# Sensor_Connection.net
KiCad netlist of a schematic drawn in Altium Designer
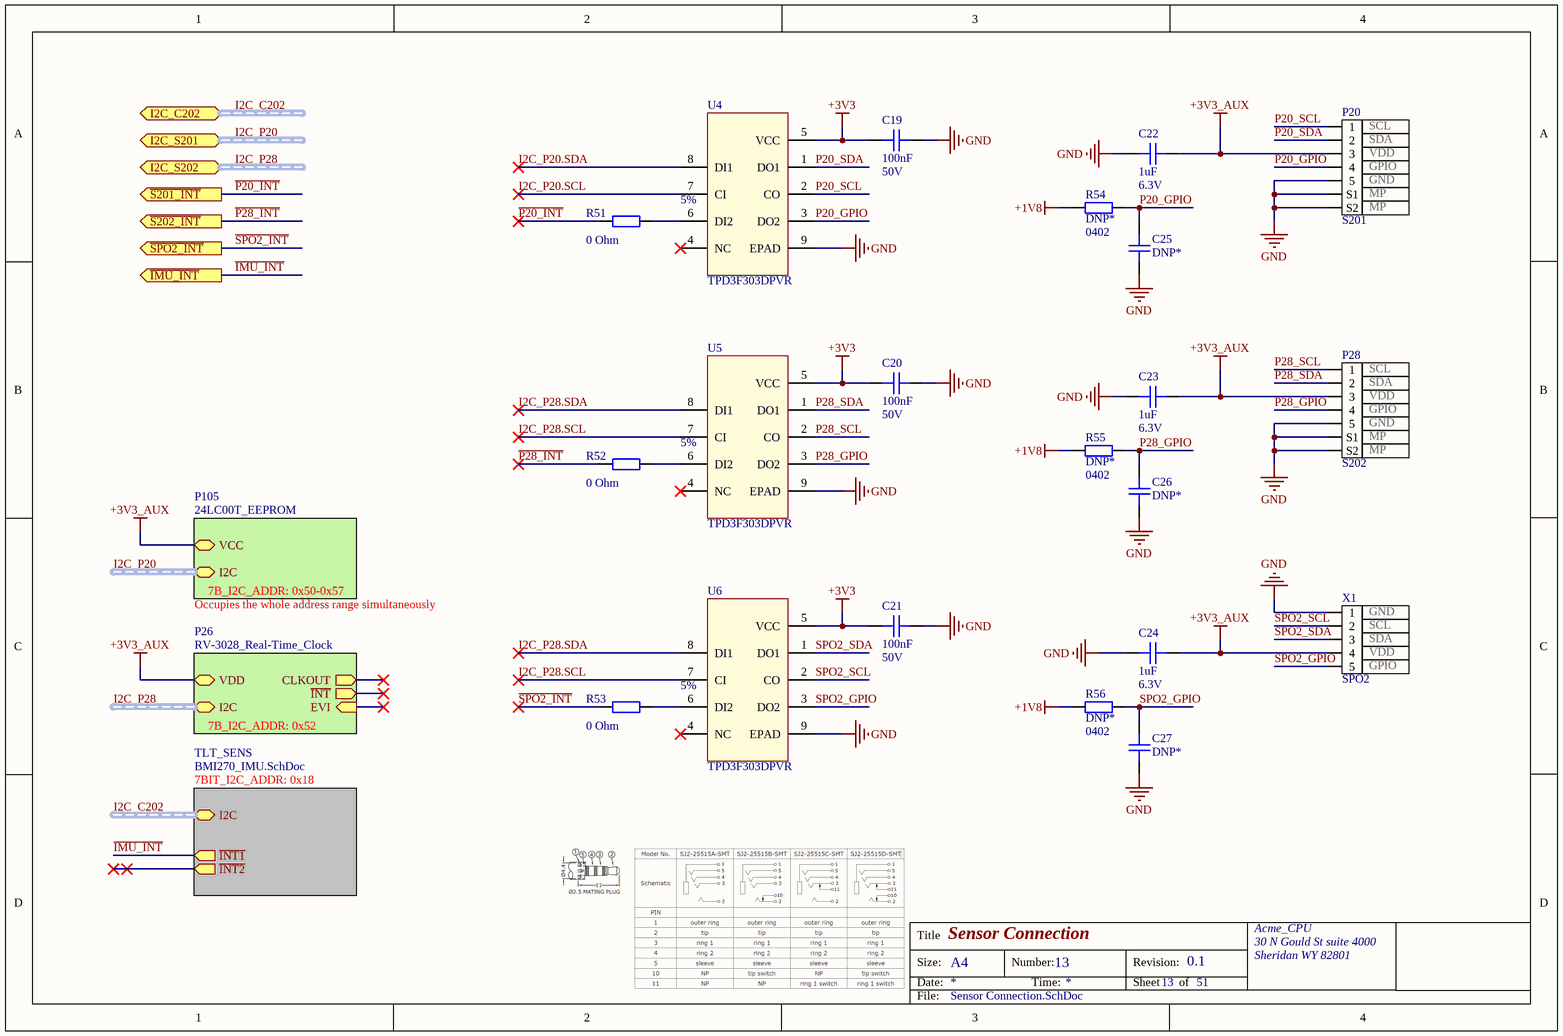
[diagram p0: Sensor Connection.SchDoc]

(export (version "E")
  (design (tool "Eeschema 10.0.6"))
  (components
    (comp (ref "C19")
      (value "CAP CER 0.1UF 50V X7R 0402")
      (footprint "C0402")
      (description "0.1µF ±10% 50V Ceramic Capacitor X7R 0402 (1005 Metric)")
      (fields
        (field (name "MANUFACTURER") "TDK")
        (field (name "MANUFACTURER PART NUMBER") "CGA2B3X7R1H104K050BB")
        (field (name "CAPACITANCE") "100nF")
        (field (name "VOLTAGE") "50V")
      )
      (libsource (lib "capacitors_smd") (part "CAP CER 0.1UF 50V X7R 0402"))
    )
    (comp (ref "C20")
      (value "CAP CER 0.1UF 50V X7R 0402")
      (footprint "C0402")
      (description "0.1µF ±10% 50V Ceramic Capacitor X7R 0402 (1005 Metric)")
      (fields
        (field (name "MANUFACTURER") "TDK")
        (field (name "MANUFACTURER PART NUMBER") "CGA2B3X7R1H104K050BB")
        (field (name "CAPACITANCE") "100nF")
        (field (name "VOLTAGE") "50V")
      )
      (libsource (lib "capacitors_smd") (part "CAP CER 0.1UF 50V X7R 0402"))
    )
    (comp (ref "C21")
      (value "CAP CER 0.1UF 50V X7R 0402")
      (footprint "C0402")
      (description "0.1µF ±10% 50V Ceramic Capacitor X7R 0402 (1005 Metric)")
      (fields
        (field (name "MANUFACTURER") "TDK")
        (field (name "MANUFACTURER PART NUMBER") "CGA2B3X7R1H104K050BB")
        (field (name "CAPACITANCE") "100nF")
        (field (name "VOLTAGE") "50V")
      )
      (libsource (lib "capacitors_smd") (part "CAP CER 0.1UF 50V X7R 0402"))
    )
    (comp (ref "C22")
      (value "CAP CER 1UF 6.3V X5R 0402")
      (footprint "C0402")
      (description "1µF ±10% 6.3V Ceramic Capacitor X5R 0402 (1005 Metric)")
      (fields
        (field (name "MANUFACTURER") "Yageo")
        (field (name "MANUFACTURER PART NUMBER") "CC0402KRX5R5BB105")
        (field (name "CAPACITANCE") "1uF")
        (field (name "VOLTAGE RATING") "6.3V")
      )
      (libsource (lib "capacitors_smd") (part "CAP CER 1UF 6.3V X5R 0402"))
    )
    (comp (ref "C23")
      (value "CAP CER 1UF 6.3V X5R 0402")
      (footprint "C0402")
      (description "1µF ±10% 6.3V Ceramic Capacitor X5R 0402 (1005 Metric)")
      (fields
        (field (name "MANUFACTURER") "Yageo")
        (field (name "MANUFACTURER PART NUMBER") "CC0402KRX5R5BB105")
        (field (name "CAPACITANCE") "1uF")
        (field (name "VOLTAGE RATING") "6.3V")
      )
      (libsource (lib "capacitors_smd") (part "CAP CER 1UF 6.3V X5R 0402"))
    )
    (comp (ref "C24")
      (value "CAP CER 1UF 6.3V X5R 0402")
      (footprint "C0402")
      (description "1µF ±10% 6.3V Ceramic Capacitor X5R 0402 (1005 Metric)")
      (fields
        (field (name "MANUFACTURER") "Yageo")
        (field (name "MANUFACTURER PART NUMBER") "CC0402KRX5R5BB105")
        (field (name "CAPACITANCE") "1uF")
        (field (name "VOLTAGE RATING") "6.3V")
      )
      (libsource (lib "capacitors_smd") (part "CAP CER 1UF 6.3V X5R 0402"))
    )
    (comp (ref "C25")
      (value "DNP*")
      (footprint "C0402")
      (description "Placeholder for a 0402 capacitor")
      (libsource (lib "capacitors_smd") (part "CAP CER NO_BOM 0402"))
    )
    (comp (ref "C26")
      (value "DNP*")
      (footprint "C0402")
      (description "Placeholder for a 0402 capacitor")
      (libsource (lib "capacitors_smd") (part "CAP CER NO_BOM 0402"))
    )
    (comp (ref "C27")
      (value "DNP*")
      (footprint "C0402")
      (description "Placeholder for a 0402 capacitor")
      (libsource (lib "capacitors_smd") (part "CAP CER NO_BOM 0402"))
    )
    (comp (ref "P20")
      (value "S201")
      (footprint "CONN_0545500571")
      (description "5 Position FFC, FPC Connector Contacts, Top 0.020\" (0.50mm) Surface Mount, Right Angle")
      (fields
        (field (name "MANUFACTURER") "Molex")
        (field (name "MANUFACTURER PART NUMBER") "0545500571")
        (field (name "PIN_1") "SCL")
        (field (name "PIN_2") "SDA")
        (field (name "PIN_3") "VDD")
        (field (name "PIN_4") "GPIO")
        (field (name "PIN_5") "GND")
        (field (name "PIN_MP1") "MP")
        (field (name "PIN_MP2") "MP")
      )
      (libsource (lib "connectors_ffc") (part "CONN FFC FPC TOP 5POS 0.50MM R/A"))
    )
    (comp (ref "P28")
      (value "S202")
      (footprint "CONN_0545500571")
      (description "5 Position FFC, FPC Connector Contacts, Top 0.020\" (0.50mm) Surface Mount, Right Angle")
      (fields
        (field (name "MANUFACTURER") "Molex")
        (field (name "MANUFACTURER PART NUMBER") "0545500571")
        (field (name "PIN_1") "SCL")
        (field (name "PIN_2") "SDA")
        (field (name "PIN_3") "VDD")
        (field (name "PIN_4") "GPIO")
        (field (name "PIN_5") "GND")
        (field (name "PIN_MP1") "MP")
        (field (name "PIN_MP2") "MP")
      )
      (libsource (lib "connectors_ffc") (part "CONN FFC FPC TOP 5POS 0.50MM R/A"))
    )
    (comp (ref "R51")
      (value "RES SMD 0 OHM JUMPER 1/16W 0402")
      (footprint "R0402")
      (description "0 Ohms Jumper 0.063W, 1/16W Chip Resistor 0402 (1005 Metric) Moisture Resistant Thick Film")
      (fields
        (field (name "MANUFACTURER") "Yageo")
        (field (name "MANUFACTURER PART NUMBER") "RC0402JR-070RL")
        (field (name "TOLERANCE") "5%")
        (field (name "RESISTANCE") "0 Ohm")
      )
      (libsource (lib "resistors_smd") (part "RES SMD 0 OHM JUMPER 1/16W 0402"))
    )
    (comp (ref "R52")
      (value "RES SMD 0 OHM JUMPER 1/16W 0402")
      (footprint "R0402")
      (description "0 Ohms Jumper 0.063W, 1/16W Chip Resistor 0402 (1005 Metric) Moisture Resistant Thick Film")
      (fields
        (field (name "MANUFACTURER") "Yageo")
        (field (name "MANUFACTURER PART NUMBER") "RC0402JR-070RL")
        (field (name "TOLERANCE") "5%")
        (field (name "RESISTANCE") "0 Ohm")
      )
      (libsource (lib "resistors_smd") (part "RES SMD 0 OHM JUMPER 1/16W 0402"))
    )
    (comp (ref "R53")
      (value "RES SMD 0 OHM JUMPER 1/16W 0402")
      (footprint "R0402")
      (description "0 Ohms Jumper 0.063W, 1/16W Chip Resistor 0402 (1005 Metric) Moisture Resistant Thick Film")
      (fields
        (field (name "MANUFACTURER") "Yageo")
        (field (name "MANUFACTURER PART NUMBER") "RC0402JR-070RL")
        (field (name "TOLERANCE") "5%")
        (field (name "RESISTANCE") "0 Ohm")
      )
      (libsource (lib "resistors_smd") (part "RES SMD 0 OHM JUMPER 1/16W 0402"))
    )
    (comp (ref "R54")
      (value "DNP*")
      (footprint "R0402")
      (description "Placeholder for a 0402 resistor")
      (fields (field (name "CASE/PACKAGE") "0402"))
      (libsource (lib "resistors_smd") (part "RES SMD NO BOM 0402"))
    )
    (comp (ref "R55")
      (value "DNP*")
      (footprint "R0402")
      (description "Placeholder for a 0402 resistor")
      (fields (field (name "CASE/PACKAGE") "0402"))
      (libsource (lib "resistors_smd") (part "RES SMD NO BOM 0402"))
    )
    (comp (ref "R56")
      (value "DNP*")
      (footprint "R0402")
      (description "Placeholder for a 0402 resistor")
      (fields (field (name "CASE/PACKAGE") "0402"))
      (libsource (lib "resistors_smd") (part "RES SMD NO BOM 0402"))
    )
    (comp (ref "U4")
      (value "TPD3F303DPVR")
      (footprint "DPV8_1P7X0P4")
      (description "RC (Pi) EMI Filter 2nd Order Low Pass 3 Channel R = 47Ohms, 100Ohms, C = 20pF  8-UFDFN Exposed Pad")
      (fields (field (name "MANUFACTURER") "Texas Instruments"))
      (libsource (lib "diodes_tvs") (part "FILTER RC(PI) ESD SMD  8-UFDFN EP"))
    )
    (comp (ref "U5")
      (value "TPD3F303DPVR")
      (footprint "DPV8_1P7X0P4")
      (description "RC (Pi) EMI Filter 2nd Order Low Pass 3 Channel R = 47Ohms, 100Ohms, C = 20pF  8-UFDFN Exposed Pad")
      (fields (field (name "MANUFACTURER") "Texas Instruments"))
      (libsource (lib "diodes_tvs") (part "FILTER RC(PI) ESD SMD  8-UFDFN EP"))
    )
    (comp (ref "U6")
      (value "TPD3F303DPVR")
      (footprint "DPV8_1P7X0P4")
      (description "RC (Pi) EMI Filter 2nd Order Low Pass 3 Channel R = 47Ohms, 100Ohms, C = 20pF  8-UFDFN Exposed Pad")
      (fields (field (name "MANUFACTURER") "Texas Instruments"))
      (libsource (lib "diodes_tvs") (part "FILTER RC(PI) ESD SMD  8-UFDFN EP"))
    )
    (comp (ref "X1")
      (value "SPO2")
      (footprint "CUI_SJ2-25515A-SMT-TR")
      (fields
        (field (name "MANUFACTURER") "CUI")
        (field (name "MANUFACTURER PART NUMBER") "SJ2-25515A-SMT-TR")
        (field (name "PIN_1") "GND")
        (field (name "PIN_2") "SCL")
        (field (name "PIN_3") "SDA")
        (field (name "PIN_4") "VDD")
        (field (name "PIN_5") "GPIO")
      )
      (libsource (lib "connectors_audio") (part "AUDIO JACK SJ2-25515A 2.5 MM RT 5 CONDUC"))
    )
  )
  (nets
    (net (code "4") (name "+1V8") (class "Default")
      (node (ref "R54") (pin "2") (pinfunction "2_2") (pintype "passive"))
      (node (ref "R55") (pin "2") (pinfunction "2_2") (pintype "passive"))
      (node (ref "R56") (pin "2") (pinfunction "2_2") (pintype "passive"))
    )
    (net (code "5") (name "+3V3") (class "Default")
      (node (ref "C19") (pin "1") (pinfunction "1_1") (pintype "passive"))
      (node (ref "C20") (pin "1") (pinfunction "1_1") (pintype "passive"))
      (node (ref "C21") (pin "1") (pinfunction "1_1") (pintype "passive"))
      (node (ref "U4") (pin "5") (pinfunction "VCC_5") (pintype "power_in"))
      (node (ref "U5") (pin "5") (pinfunction "VCC_5") (pintype "power_in"))
      (node (ref "U6") (pin "5") (pinfunction "VCC_5") (pintype "power_in"))
    )
    (net (code "6") (name "+3V3_AUX") (class "Default")
      (node (ref "C22") (pin "2") (pinfunction "2_2") (pintype "passive"))
      (node (ref "C23") (pin "2") (pinfunction "2_2") (pintype "passive"))
      (node (ref "C24") (pin "2") (pinfunction "2_2") (pintype "passive"))
      (node (ref "P20") (pin "3") (pinfunction "3_3") (pintype "passive"))
      (node (ref "P28") (pin "3") (pinfunction "3_3") (pintype "passive"))
      (node (ref "X1") (pin "4") (pinfunction "4_4") (pintype "passive"))
    )
    (net (code "9") (name "/I2C_P20.SCL") (class "Default")
      (node (ref "U4") (pin "7") (pinfunction "CI_7") (pintype "passive+no_connect"))
    )
    (net (code "10") (name "/I2C_P20.SDA") (class "Default")
      (node (ref "U4") (pin "8") (pinfunction "DI1_8") (pintype "passive+no_connect"))
    )
    (net (code "11") (name "/I2C_P28.SCL") (class "Default")
      (node (ref "U5") (pin "7") (pinfunction "CI_7") (pintype "passive"))
      (node (ref "U6") (pin "7") (pinfunction "CI_7") (pintype "passive"))
    )
    (net (code "12") (name "/I2C_P28.SDA") (class "Default")
      (node (ref "U5") (pin "8") (pinfunction "DI1_8") (pintype "passive"))
      (node (ref "U6") (pin "8") (pinfunction "DI1_8") (pintype "passive"))
    )
    (net (code "16") (name "/P20_GPIO") (class "Default")
      (node (ref "C25") (pin "2") (pinfunction "2_2") (pintype "passive"))
      (node (ref "P20") (pin "4") (pinfunction "4_4") (pintype "passive"))
      (node (ref "R54") (pin "1") (pinfunction "1_1") (pintype "passive"))
      (node (ref "U4") (pin "3") (pinfunction "DO2_3") (pintype "passive"))
    )
    (net (code "17") (name "/P20_INT") (class "Default")
      (node (ref "R51") (pin "1") (pinfunction "1_1") (pintype "passive+no_connect"))
    )
    (net (code "18") (name "/P20_SCL") (class "Default")
      (node (ref "P20") (pin "1") (pinfunction "1_1") (pintype "passive"))
      (node (ref "U4") (pin "2") (pinfunction "CO_2") (pintype "passive"))
    )
    (net (code "19") (name "/P20_SDA") (class "Default")
      (node (ref "P20") (pin "2") (pinfunction "2_2") (pintype "passive"))
      (node (ref "U4") (pin "1") (pinfunction "DO1_1") (pintype "passive"))
    )
    (net (code "20") (name "/P28_GPIO") (class "Default")
      (node (ref "C26") (pin "2") (pinfunction "2_2") (pintype "passive"))
      (node (ref "P28") (pin "4") (pinfunction "4_4") (pintype "passive"))
      (node (ref "R55") (pin "1") (pinfunction "1_1") (pintype "passive"))
      (node (ref "U5") (pin "3") (pinfunction "DO2_3") (pintype "passive"))
    )
    (net (code "21") (name "/P28_INT") (class "Default")
      (node (ref "R52") (pin "1") (pinfunction "1_1") (pintype "passive"))
    )
    (net (code "22") (name "/P28_SCL") (class "Default")
      (node (ref "P28") (pin "1") (pinfunction "1_1") (pintype "passive"))
      (node (ref "U5") (pin "2") (pinfunction "CO_2") (pintype "passive"))
    )
    (net (code "23") (name "/P28_SDA") (class "Default")
      (node (ref "P28") (pin "2") (pinfunction "2_2") (pintype "passive"))
      (node (ref "U5") (pin "1") (pinfunction "DO1_1") (pintype "passive"))
    )
    (net (code "24") (name "/SPO2_GPIO") (class "Default")
      (node (ref "C27") (pin "2") (pinfunction "2_2") (pintype "passive"))
      (node (ref "R56") (pin "1") (pinfunction "1_1") (pintype "passive"))
      (node (ref "U6") (pin "3") (pinfunction "DO2_3") (pintype "passive"))
      (node (ref "X1") (pin "5") (pinfunction "5_5") (pintype "passive"))
    )
    (net (code "25") (name "/SPO2_INT") (class "Default")
      (node (ref "R53") (pin "1") (pinfunction "1_1") (pintype "passive"))
    )
    (net (code "26") (name "/SPO2_SCL") (class "Default")
      (node (ref "U6") (pin "2") (pinfunction "CO_2") (pintype "passive"))
      (node (ref "X1") (pin "2") (pinfunction "2_2") (pintype "passive"))
    )
    (net (code "27") (name "/SPO2_SDA") (class "Default")
      (node (ref "U6") (pin "1") (pinfunction "DO1_1") (pintype "passive"))
      (node (ref "X1") (pin "3") (pinfunction "3_3") (pintype "passive"))
    )
    (net (code "31") (name "GND") (class "Default")
      (node (ref "C19") (pin "2") (pinfunction "2_2") (pintype "passive"))
      (node (ref "C20") (pin "2") (pinfunction "2_2") (pintype "passive"))
      (node (ref "C21") (pin "2") (pinfunction "2_2") (pintype "passive"))
      (node (ref "C22") (pin "1") (pinfunction "1_1") (pintype "passive"))
      (node (ref "C23") (pin "1") (pinfunction "1_1") (pintype "passive"))
      (node (ref "C24") (pin "1") (pinfunction "1_1") (pintype "passive"))
      (node (ref "C25") (pin "1") (pinfunction "1_1") (pintype "passive"))
      (node (ref "C26") (pin "1") (pinfunction "1_1") (pintype "passive"))
      (node (ref "C27") (pin "1") (pinfunction "1_1") (pintype "passive"))
      (node (ref "P20") (pin "0") (pinfunction "S1_0") (pintype "passive"))
      (node (ref "P20") (pin "5") (pinfunction "5_5") (pintype "passive"))
      (node (ref "P28") (pin "0") (pinfunction "S1_0") (pintype "passive"))
      (node (ref "P28") (pin "5") (pinfunction "5_5") (pintype "passive"))
      (node (ref "U4") (pin "9") (pinfunction "EPAD_9") (pintype "passive"))
      (node (ref "U5") (pin "9") (pinfunction "EPAD_9") (pintype "passive"))
      (node (ref "U6") (pin "9") (pinfunction "EPAD_9") (pintype "passive"))
      (node (ref "X1") (pin "1") (pinfunction "1_1") (pintype "passive"))
    )
    (net (code "32") (name "Net-(U4-DI2)") (class "Default")
      (node (ref "R51") (pin "2") (pinfunction "2_2") (pintype "passive"))
      (node (ref "U4") (pin "6") (pinfunction "DI2_6") (pintype "passive"))
    )
    (net (code "33") (name "Net-(U5-DI2)") (class "Default")
      (node (ref "R52") (pin "2") (pinfunction "2_2") (pintype "passive"))
      (node (ref "U5") (pin "6") (pinfunction "DI2_6") (pintype "passive"))
    )
    (net (code "34") (name "Net-(U6-DI2)") (class "Default")
      (node (ref "R53") (pin "2") (pinfunction "2_2") (pintype "passive"))
      (node (ref "U6") (pin "6") (pinfunction "DI2_6") (pintype "passive"))
    )
    (net (code "35") (name "unconnected-(U4-NC-Pad4)") (class "Default")
      (node (ref "U4") (pin "4") (pinfunction "NC_4") (pintype "passive+no_connect"))
    )
    (net (code "36") (name "unconnected-(U5-NC-Pad4)") (class "Default")
      (node (ref "U5") (pin "4") (pinfunction "NC_4") (pintype "passive+no_connect"))
    )
    (net (code "37") (name "unconnected-(U6-NC-Pad4)") (class "Default")
      (node (ref "U6") (pin "4") (pinfunction "NC_4") (pintype "passive+no_connect"))
    )
  )
)
